# uC_ui.net
KiCad netlist of a schematic drawn in Altium Designer
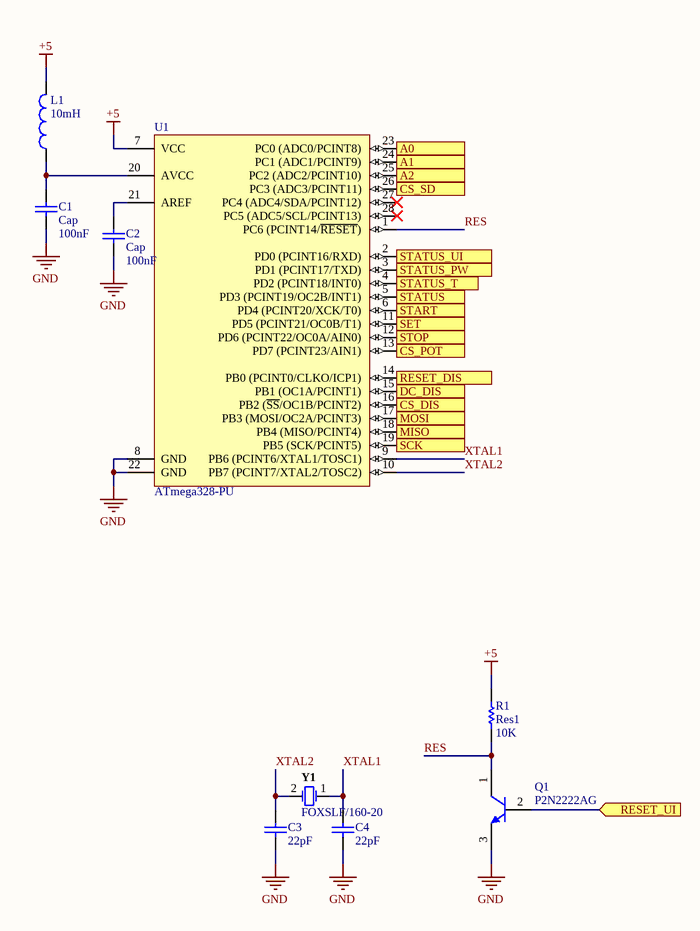
[diagram p0: uC_ui.SchDoc]

(export (version "E")
  (design (tool "Eeschema 10.0.6"))
  (components
    (comp (ref "C1")
      (value "Cap")
      (footprint "RAD-0.3")
      (description "Capacitor")
      (fields (field (name "ALTIUM_VALUE") "100nF") (field (name "PUBLISHER") "Altium Limited"))
      (libsource (lib "Miscellaneous Devices") (part "Cap"))
    )
    (comp (ref "C2")
      (value "Cap")
      (footprint "RAD-0.3")
      (description "Capacitor")
      (fields (field (name "ALTIUM_VALUE") "100nF") (field (name "PUBLISHER") "Altium Limited"))
      (libsource (lib "Miscellaneous Devices") (part "Cap"))
    )
    (comp (ref "C3")
      (value "22pF")
      (footprint "RAD-0.3")
      (description "Capacitor")
      (fields (field (name "Comment") "Cap") (field (name "PUBLISHER") "Altium Limited"))
      (libsource (lib "Miscellaneous Devices") (part "Cap"))
    )
    (comp (ref "C4")
      (value "22pF")
      (footprint "RAD-0.3")
      (description "Capacitor")
      (fields (field (name "Comment") "Cap") (field (name "PUBLISHER") "Altium Limited"))
      (libsource (lib "Miscellaneous Devices") (part "Cap"))
    )
    (comp (ref "L1")
      (value "10mH")
      (footprint "INDR62-500-1100X850X1100")
      (description "Radial Inductor, 10 uH, +/- 10%, 3 A, -55 to 105 degC, 2-Pin THD, RoHS, Bulk")
      (libsource (lib "Altium Content Vault") (part "IND-2"))
    )
    (comp (ref "Q1")
      (value "P2N2222AG")
      (footprint "ONSC-TO-92-3-29-11")
      (description "Amplifier Transistor, NPN Silicon, 3-Pin TO-92, Pb-Free, Bulk Box")
      (fields (field (name "MANUFACTURER") "On Semiconductor"))
      (libsource (lib "Altium Content Vault") (part "ONSC-NPN-C1B2E3-3"))
    )
    (comp (ref "R1")
      (value "Res1")
      (footprint "AXIAL-0.4")
      (description "Resistor")
      (fields (field (name "ALTIUM_VALUE") "10K") (field (name "PUBLISHER") "Altium Limited"))
      (libsource (lib "Miscellaneous Devices") (part "Res1"))
    )
    (comp (ref "U1")
      (value "ATmega328-PU")
      (footprint "28P3")
      (libsource (lib "Altium Content Vault") (part "MC-8B-ATM48-IL28"))
    )
    (comp (ref "Y1")
      (value "FOXSLF/160-20")
      (footprint "FOX-FOXSLF160-20")
      (description "Resistance Weld Thru-Hole Crystal, 16 MHz, -20 to 70 degC, 2-Pin THD, RoHS, Bulk")
      (fields (field (name "TOLERANCE") "1%"))
      (libsource (lib "Altium Content Vault") (part "XTAL-1-2-2"))
    )
  )
  (nets
    (net (code "1") (name "+5") (class "Default")
      (node (ref "L1") (pin "2") (pinfunction "2_2") (pintype "passive"))
      (node (ref "R1") (pin "2") (pinfunction "2_2") (pintype "passive"))
      (node (ref "U1") (pin "7") (pinfunction "VCC_7") (pintype "power_in"))
    )
    (net (code "2") (name "/A0") (class "Default")
      (node (ref "U1") (pin "23") (pinfunction "PC0_(ADC0/PCINT8)_23") (pintype "bidirectional"))
    )
    (net (code "3") (name "/A1") (class "Default")
      (node (ref "U1") (pin "24") (pinfunction "PC1_(ADC1/PCINT9)_24") (pintype "bidirectional"))
    )
    (net (code "4") (name "/A2") (class "Default")
      (node (ref "U1") (pin "25") (pinfunction "PC2_(ADC2/PCINT10)_25") (pintype "bidirectional"))
    )
    (net (code "5") (name "/CS_DIS") (class "Default")
      (node (ref "U1") (pin "16") (pinfunction "PB2_(~{SS}/OC1B/PCINT2)_16") (pintype "bidirectional"))
    )
    (net (code "6") (name "/CS_POT") (class "Default")
      (node (ref "U1") (pin "13") (pinfunction "PD7_(PCINT23/AIN1)_13") (pintype "bidirectional"))
    )
    (net (code "7") (name "/CS_SD") (class "Default")
      (node (ref "U1") (pin "26") (pinfunction "PC3_(ADC3/PCINT11)_26") (pintype "bidirectional"))
    )
    (net (code "8") (name "/DC_DIS") (class "Default")
      (node (ref "U1") (pin "15") (pinfunction "PB1_(OC1A/PCINT1)_15") (pintype "bidirectional"))
    )
    (net (code "9") (name "/MISO") (class "Default")
      (node (ref "U1") (pin "18") (pinfunction "PB4_(MISO/PCINT4)_18") (pintype "bidirectional"))
    )
    (net (code "10") (name "/MOSI") (class "Default")
      (node (ref "U1") (pin "17") (pinfunction "PB3_(MOSI/OC2A/PCINT3)_17") (pintype "bidirectional"))
    )
    (net (code "11") (name "/RES") (class "Default")
      (node (ref "Q1") (pin "1") (pinfunction "C_1") (pintype "passive"))
      (node (ref "R1") (pin "1") (pinfunction "1_1") (pintype "passive"))
      (node (ref "U1") (pin "1") (pinfunction "PC6_(PCINT14/~{RESET})_1") (pintype "bidirectional"))
    )
    (net (code "12") (name "/RESET_DIS") (class "Default")
      (node (ref "U1") (pin "14") (pinfunction "PB0_(PCINT0/CLKO/ICP1)_14") (pintype "bidirectional"))
    )
    (net (code "13") (name "/RESET_UI") (class "Default")
      (node (ref "Q1") (pin "2") (pinfunction "B_2") (pintype "passive"))
    )
    (net (code "14") (name "/SCK") (class "Default")
      (node (ref "U1") (pin "19") (pinfunction "PB5_(SCK/PCINT5)_19") (pintype "bidirectional"))
    )
    (net (code "15") (name "/SET") (class "Default")
      (node (ref "U1") (pin "11") (pinfunction "PD5_(PCINT21/OC0B/T1)_11") (pintype "bidirectional"))
    )
    (net (code "16") (name "/START") (class "Default")
      (node (ref "U1") (pin "6") (pinfunction "PD4_(PCINT20/XCK/T0)_6") (pintype "bidirectional"))
    )
    (net (code "17") (name "/STATUS") (class "Default")
      (node (ref "U1") (pin "5") (pinfunction "PD3_(PCINT19/OC2B/INT1)_5") (pintype "bidirectional"))
    )
    (net (code "18") (name "/STATUS_PW") (class "Default")
      (node (ref "U1") (pin "3") (pinfunction "PD1_(PCINT17/TXD)_3") (pintype "bidirectional"))
    )
    (net (code "19") (name "/STATUS_T") (class "Default")
      (node (ref "U1") (pin "4") (pinfunction "PD2_(PCINT18/INT0)_4") (pintype "bidirectional"))
    )
    (net (code "20") (name "/STATUS_UI") (class "Default")
      (node (ref "U1") (pin "2") (pinfunction "PD0_(PCINT16/RXD)_2") (pintype "bidirectional"))
    )
    (net (code "21") (name "/STOP") (class "Default")
      (node (ref "U1") (pin "12") (pinfunction "PD6_(PCINT22/OC0A/AIN0)_12") (pintype "bidirectional"))
    )
    (net (code "22") (name "/XTAL1") (class "Default")
      (node (ref "C4") (pin "2") (pinfunction "2_2") (pintype "passive"))
      (node (ref "U1") (pin "9") (pinfunction "PB6_(PCINT6/XTAL1/TOSC1)_9") (pintype "bidirectional"))
      (node (ref "Y1") (pin "1") (pinfunction "1_1") (pintype "passive"))
    )
    (net (code "23") (name "/XTAL2") (class "Default")
      (node (ref "C3") (pin "2") (pinfunction "2_2") (pintype "passive"))
      (node (ref "U1") (pin "10") (pinfunction "PB7_(PCINT7/XTAL2/TOSC2)_10") (pintype "bidirectional"))
      (node (ref "Y1") (pin "2") (pinfunction "2_2") (pintype "passive"))
    )
    (net (code "24") (name "GND") (class "Default")
      (node (ref "C1") (pin "1") (pinfunction "1_1") (pintype "passive"))
      (node (ref "C2") (pin "1") (pinfunction "1_1") (pintype "passive"))
      (node (ref "C3") (pin "1") (pinfunction "1_1") (pintype "passive"))
      (node (ref "C4") (pin "1") (pinfunction "1_1") (pintype "passive"))
      (node (ref "Q1") (pin "3") (pinfunction "E_3") (pintype "passive"))
      (node (ref "U1") (pin "22") (pinfunction "GND_22") (pintype "power_in"))
      (node (ref "U1") (pin "8") (pinfunction "GND_8") (pintype "power_in"))
    )
    (net (code "25") (name "Net-(U1-AREF)") (class "Default")
      (node (ref "C2") (pin "2") (pinfunction "2_2") (pintype "passive"))
      (node (ref "U1") (pin "21") (pinfunction "AREF_21") (pintype "power_in"))
    )
    (net (code "26") (name "Net-(U1-AVCC)") (class "Default")
      (node (ref "C1") (pin "2") (pinfunction "2_2") (pintype "passive"))
      (node (ref "L1") (pin "1") (pinfunction "1_1") (pintype "passive"))
      (node (ref "U1") (pin "20") (pinfunction "AVCC_20") (pintype "power_in"))
    )
    (net (code "27") (name "unconnected-(U1-PC4_(ADC4{slash}SDA{slash}PCINT12)-Pad27)") (class "Default")
      (node (ref "U1") (pin "27") (pinfunction "PC4_(ADC4/SDA/PCINT12)_27") (pintype "bidirectional+no_connect"))
    )
    (net (code "28") (name "unconnected-(U1-PC5_(ADC5{slash}SCL{slash}PCINT13)-Pad28)") (class "Default")
      (node (ref "U1") (pin "28") (pinfunction "PC5_(ADC5/SCL/PCINT13)_28") (pintype "bidirectional+no_connect"))
    )
  )
)
